# Arctos_65_V1.net
KiCad netlist of a schematic drawn in EAGLE
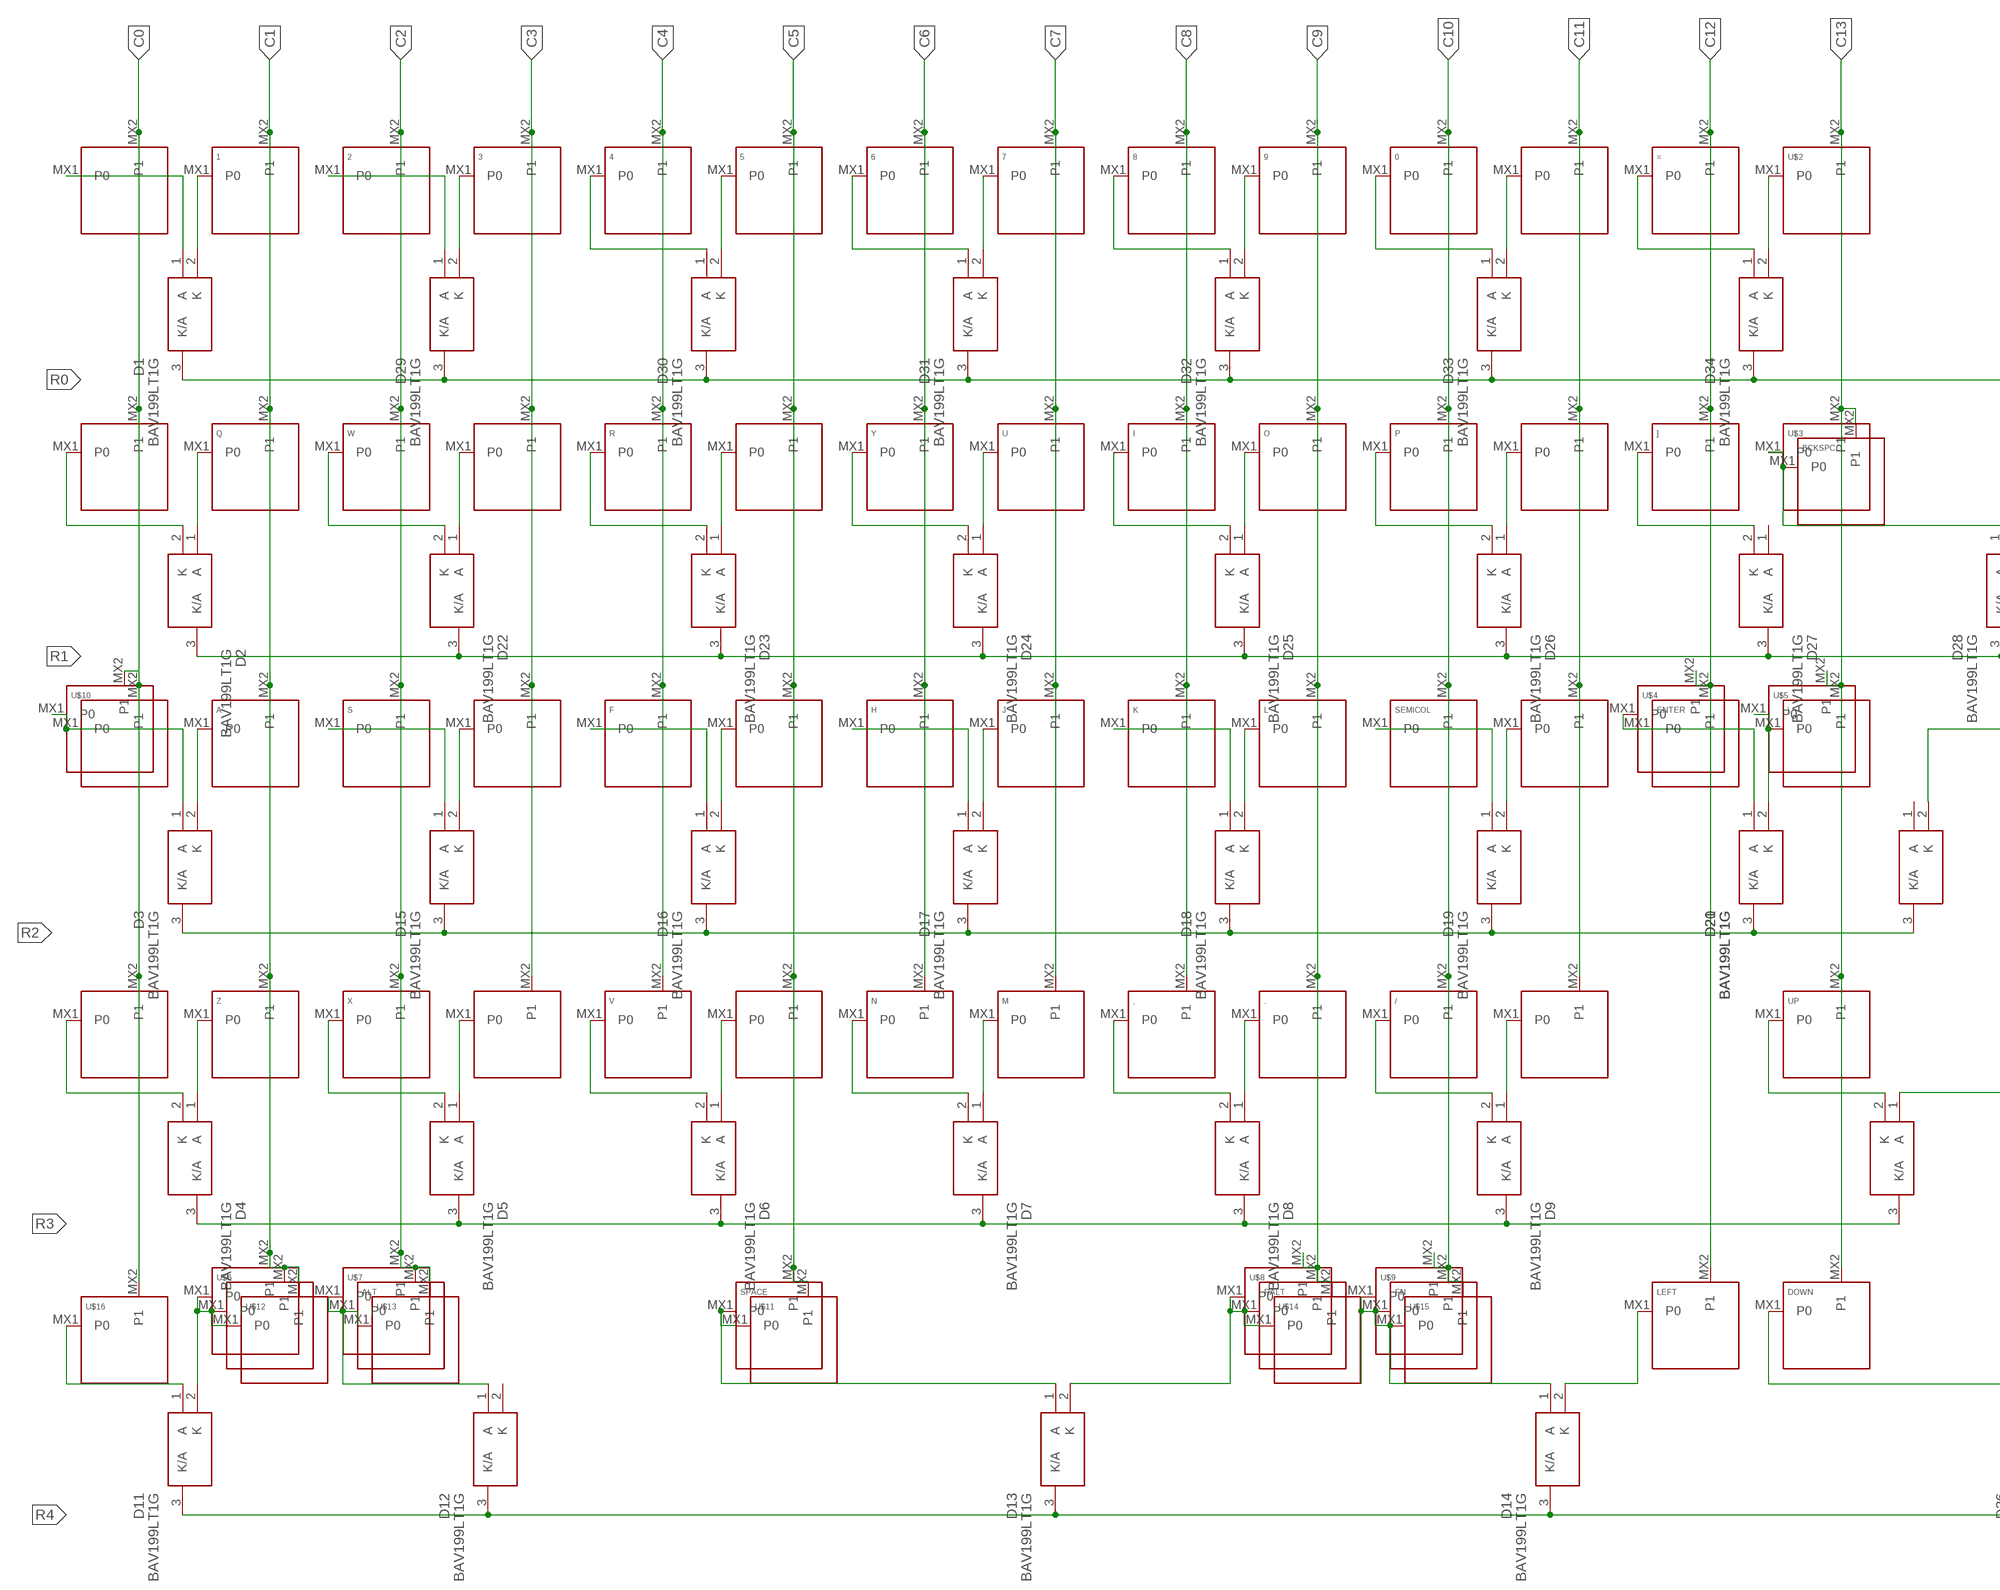
[diagram p0: schematic, sheet 1, part 1 of 2]
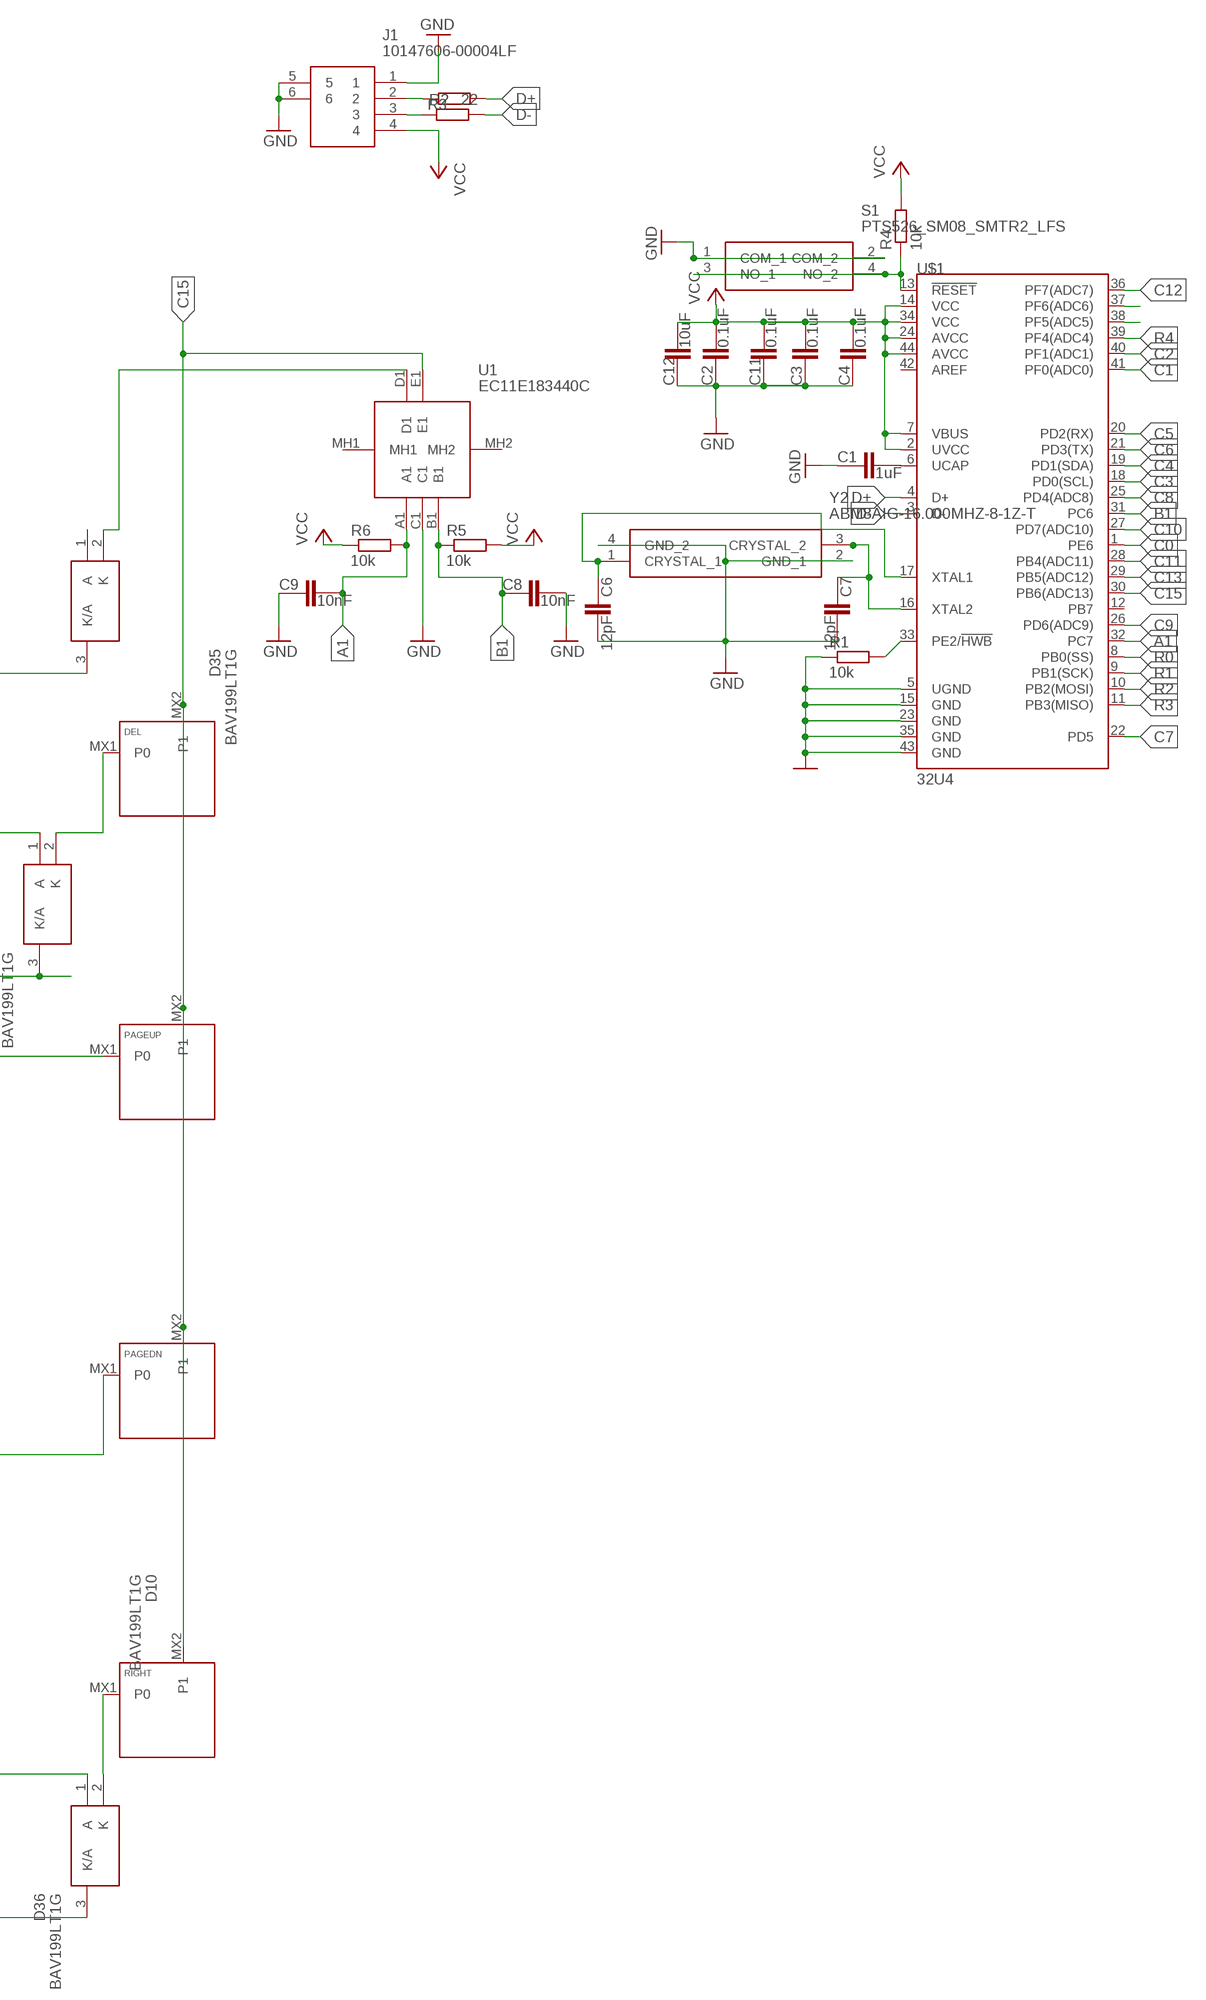
[diagram p1: schematic, sheet 1, part 2 of 2]

(export (version "E")
  (design (tool "Eeschema 10.0.6"))
  (components
    (comp (ref "'")
      (value "KEYSWITCH-PLAIN-MX-1U")
      (footprint "eagle-import:MX-1U")
      (libsource (lib "eagle-import") (part "KEYSWITCH-PLAIN-MX-1U"))
    )
    (comp (ref ",")
      (value "KEYSWITCH-PLAIN-MX-1U")
      (footprint "eagle-import:MX-1U")
      (libsource (lib "eagle-import") (part "KEYSWITCH-PLAIN-MX-1U"))
    )
    (comp (ref "-")
      (value "KEYSWITCH-PLAIN-MX-1U")
      (footprint "eagle-import:MX-1U")
      (libsource (lib "eagle-import") (part "KEYSWITCH-PLAIN-MX-1U"))
    )
    (comp (ref ".")
      (value "KEYSWITCH-PLAIN-MX-1U")
      (footprint "eagle-import:MX-1U")
      (libsource (lib "eagle-import") (part "KEYSWITCH-PLAIN-MX-1U"))
    )
    (comp (ref "/")
      (value "KEYSWITCH-PLAIN-MX-1U")
      (footprint "eagle-import:MX-1U")
      (libsource (lib "eagle-import") (part "KEYSWITCH-PLAIN-MX-1U"))
    )
    (comp (ref "0")
      (value "KEYSWITCH-PLAIN-MX-1U")
      (footprint "eagle-import:MX-1U")
      (libsource (lib "eagle-import") (part "KEYSWITCH-PLAIN-MX-1U"))
    )
    (comp (ref "1")
      (value "KEYSWITCH-PLAIN-MX-1U")
      (footprint "eagle-import:MX-1U")
      (libsource (lib "eagle-import") (part "KEYSWITCH-PLAIN-MX-1U"))
    )
    (comp (ref "2")
      (value "KEYSWITCH-PLAIN-MX-1U")
      (footprint "eagle-import:MX-1U")
      (libsource (lib "eagle-import") (part "KEYSWITCH-PLAIN-MX-1U"))
    )
    (comp (ref "3")
      (value "KEYSWITCH-PLAIN-MX-1U")
      (footprint "eagle-import:MX-1U")
      (libsource (lib "eagle-import") (part "KEYSWITCH-PLAIN-MX-1U"))
    )
    (comp (ref "4")
      (value "KEYSWITCH-PLAIN-MX-1U")
      (footprint "eagle-import:MX-1U")
      (libsource (lib "eagle-import") (part "KEYSWITCH-PLAIN-MX-1U"))
    )
    (comp (ref "5")
      (value "KEYSWITCH-PLAIN-MX-1U")
      (footprint "eagle-import:MX-1U")
      (libsource (lib "eagle-import") (part "KEYSWITCH-PLAIN-MX-1U"))
    )
    (comp (ref "6")
      (value "KEYSWITCH-PLAIN-MX-1U")
      (footprint "eagle-import:MX-1U")
      (libsource (lib "eagle-import") (part "KEYSWITCH-PLAIN-MX-1U"))
    )
    (comp (ref "7")
      (value "KEYSWITCH-PLAIN-MX-1U")
      (footprint "eagle-import:MX-1U")
      (libsource (lib "eagle-import") (part "KEYSWITCH-PLAIN-MX-1U"))
    )
    (comp (ref "8")
      (value "KEYSWITCH-PLAIN-MX-1U")
      (footprint "eagle-import:MX-1U")
      (libsource (lib "eagle-import") (part "KEYSWITCH-PLAIN-MX-1U"))
    )
    (comp (ref "9")
      (value "KEYSWITCH-PLAIN-MX-1U")
      (footprint "eagle-import:MX-1U")
      (libsource (lib "eagle-import") (part "KEYSWITCH-PLAIN-MX-1U"))
    )
    (comp (ref "=")
      (value "KEYSWITCH-PLAIN-MX-1U")
      (footprint "eagle-import:MX-1U")
      (libsource (lib "eagle-import") (part "KEYSWITCH-PLAIN-MX-1U"))
    )
    (comp (ref "A")
      (value "KEYSWITCH-PLAIN-MX-1U")
      (footprint "eagle-import:MX-1U")
      (libsource (lib "eagle-import") (part "KEYSWITCH-PLAIN-MX-1U"))
    )
    (comp (ref "ALT")
      (value "KEYSWITCH-PLAIN-MX-1U")
      (footprint "eagle-import:MX-1U")
      (libsource (lib "eagle-import") (part "KEYSWITCH-PLAIN-MX-1U"))
    )
    (comp (ref "B")
      (value "KEYSWITCH-PLAIN-MX-1U")
      (footprint "eagle-import:MX-1U")
      (libsource (lib "eagle-import") (part "KEYSWITCH-PLAIN-MX-1U"))
    )
    (comp (ref "BCKSPC")
      (value "KEYSWITCH-PLAIN-MX-2U")
      (footprint "eagle-import:MX-2U")
      (libsource (lib "eagle-import") (part "KEYSWITCH-PLAIN-MX-2U"))
    )
    (comp (ref "C")
      (value "KEYSWITCH-PLAIN-MX-1U")
      (footprint "eagle-import:MX-1U")
      (libsource (lib "eagle-import") (part "KEYSWITCH-PLAIN-MX-1U"))
    )
    (comp (ref "C1")
      (value "1uF")
      (footprint "eagle-import:C0603")
      (libsource (lib "eagle-import") (part "CAPACITOR-0603"))
    )
    (comp (ref "C2")
      (value "0.1uF")
      (footprint "eagle-import:C0603")
      (libsource (lib "eagle-import") (part "CAPACITOR-0603"))
    )
    (comp (ref "C3")
      (value "0.1uF")
      (footprint "eagle-import:C0603")
      (libsource (lib "eagle-import") (part "CAPACITOR-0603"))
    )
    (comp (ref "C4")
      (value "0.1uF")
      (footprint "eagle-import:C0603")
      (libsource (lib "eagle-import") (part "CAPACITOR-0603"))
    )
    (comp (ref "C6")
      (value "12pF")
      (footprint "eagle-import:C0603")
      (libsource (lib "eagle-import") (part "CAPACITOR-0603"))
    )
    (comp (ref "C7")
      (value "12pF")
      (footprint "eagle-import:C0603")
      (libsource (lib "eagle-import") (part "CAPACITOR-0603"))
    )
    (comp (ref "C8")
      (value "10nF")
      (footprint "eagle-import:C0603")
      (libsource (lib "eagle-import") (part "CAPACITOR-0603"))
    )
    (comp (ref "C9")
      (value "10nF")
      (footprint "eagle-import:C0603")
      (libsource (lib "eagle-import") (part "CAPACITOR-0603"))
    )
    (comp (ref "C11")
      (value "0.1uF")
      (footprint "eagle-import:C0603")
      (libsource (lib "eagle-import") (part "CAPACITOR-0603"))
    )
    (comp (ref "C12")
      (value "10uF")
      (footprint "eagle-import:C0603")
      (libsource (lib "eagle-import") (part "CAPACITOR-0603"))
    )
    (comp (ref "CAPS")
      (value "KEYSWITCH-PLAIN-MX-1U")
      (footprint "eagle-import:MX-1U")
      (libsource (lib "eagle-import") (part "KEYSWITCH-PLAIN-MX-1U"))
    )
    (comp (ref "D")
      (value "KEYSWITCH-PLAIN-MX-1U")
      (footprint "eagle-import:MX-1U")
      (libsource (lib "eagle-import") (part "KEYSWITCH-PLAIN-MX-1U"))
    )
    (comp (ref "D1")
      (value "BAV199LT1G")
      (footprint "eagle-import:SOT96P237X111-3N")
      (fields (field (name "MOUSER_PART_NUMBER") "863-BAV199LT1G"))
      (libsource (lib "eagle-import") (part "BAV199LT1G"))
    )
    (comp (ref "D2")
      (value "BAV199LT1G")
      (footprint "eagle-import:SOT96P237X111-3N")
      (fields (field (name "MOUSER_PART_NUMBER") "863-BAV199LT1G"))
      (libsource (lib "eagle-import") (part "BAV199LT1G"))
    )
    (comp (ref "D3")
      (value "BAV199LT1G")
      (footprint "eagle-import:SOT96P237X111-3N")
      (fields (field (name "MOUSER_PART_NUMBER") "863-BAV199LT1G"))
      (libsource (lib "eagle-import") (part "BAV199LT1G"))
    )
    (comp (ref "D4")
      (value "BAV199LT1G")
      (footprint "eagle-import:SOT96P237X111-3N")
      (fields (field (name "MOUSER_PART_NUMBER") "863-BAV199LT1G"))
      (libsource (lib "eagle-import") (part "BAV199LT1G"))
    )
    (comp (ref "D5")
      (value "BAV199LT1G")
      (footprint "eagle-import:SOT96P237X111-3N")
      (fields (field (name "MOUSER_PART_NUMBER") "863-BAV199LT1G"))
      (libsource (lib "eagle-import") (part "BAV199LT1G"))
    )
    (comp (ref "D6")
      (value "BAV199LT1G")
      (footprint "eagle-import:SOT96P237X111-3N")
      (fields (field (name "MOUSER_PART_NUMBER") "863-BAV199LT1G"))
      (libsource (lib "eagle-import") (part "BAV199LT1G"))
    )
    (comp (ref "D7")
      (value "BAV199LT1G")
      (footprint "eagle-import:SOT96P237X111-3N")
      (fields (field (name "MOUSER_PART_NUMBER") "863-BAV199LT1G"))
      (libsource (lib "eagle-import") (part "BAV199LT1G"))
    )
    (comp (ref "D8")
      (value "BAV199LT1G")
      (footprint "eagle-import:SOT96P237X111-3N")
      (fields (field (name "MOUSER_PART_NUMBER") "863-BAV199LT1G"))
      (libsource (lib "eagle-import") (part "BAV199LT1G"))
    )
    (comp (ref "D9")
      (value "BAV199LT1G")
      (footprint "eagle-import:SOT96P237X111-3N")
      (fields (field (name "MOUSER_PART_NUMBER") "863-BAV199LT1G"))
      (libsource (lib "eagle-import") (part "BAV199LT1G"))
    )
    (comp (ref "D10")
      (value "BAV199LT1G")
      (footprint "eagle-import:SOT96P237X111-3N")
      (fields (field (name "MOUSER_PART_NUMBER") "863-BAV199LT1G"))
      (libsource (lib "eagle-import") (part "BAV199LT1G"))
    )
    (comp (ref "D11")
      (value "BAV199LT1G")
      (footprint "eagle-import:SOT96P237X111-3N")
      (fields (field (name "MOUSER_PART_NUMBER") "863-BAV199LT1G"))
      (libsource (lib "eagle-import") (part "BAV199LT1G"))
    )
    (comp (ref "D12")
      (value "BAV199LT1G")
      (footprint "eagle-import:SOT96P237X111-3N")
      (fields (field (name "MOUSER_PART_NUMBER") "863-BAV199LT1G"))
      (libsource (lib "eagle-import") (part "BAV199LT1G"))
    )
    (comp (ref "D13")
      (value "BAV199LT1G")
      (footprint "eagle-import:SOT96P237X111-3N")
      (fields (field (name "MOUSER_PART_NUMBER") "863-BAV199LT1G"))
      (libsource (lib "eagle-import") (part "BAV199LT1G"))
    )
    (comp (ref "D14")
      (value "BAV199LT1G")
      (footprint "eagle-import:SOT96P237X111-3N")
      (fields (field (name "MOUSER_PART_NUMBER") "863-BAV199LT1G"))
      (libsource (lib "eagle-import") (part "BAV199LT1G"))
    )
    (comp (ref "D15")
      (value "BAV199LT1G")
      (footprint "eagle-import:SOT96P237X111-3N")
      (fields (field (name "MOUSER_PART_NUMBER") "863-BAV199LT1G"))
      (libsource (lib "eagle-import") (part "BAV199LT1G"))
    )
    (comp (ref "D16")
      (value "BAV199LT1G")
      (footprint "eagle-import:SOT96P237X111-3N")
      (fields (field (name "MOUSER_PART_NUMBER") "863-BAV199LT1G"))
      (libsource (lib "eagle-import") (part "BAV199LT1G"))
    )
    (comp (ref "D17")
      (value "BAV199LT1G")
      (footprint "eagle-import:SOT96P237X111-3N")
      (fields (field (name "MOUSER_PART_NUMBER") "863-BAV199LT1G"))
      (libsource (lib "eagle-import") (part "BAV199LT1G"))
    )
    (comp (ref "D18")
      (value "BAV199LT1G")
      (footprint "eagle-import:SOT96P237X111-3N")
      (fields (field (name "MOUSER_PART_NUMBER") "863-BAV199LT1G"))
      (libsource (lib "eagle-import") (part "BAV199LT1G"))
    )
    (comp (ref "D19")
      (value "BAV199LT1G")
      (footprint "eagle-import:SOT96P237X111-3N")
      (fields (field (name "MOUSER_PART_NUMBER") "863-BAV199LT1G"))
      (libsource (lib "eagle-import") (part "BAV199LT1G"))
    )
    (comp (ref "D20")
      (value "BAV199LT1G")
      (footprint "eagle-import:SOT96P237X111-3N")
      (fields (field (name "MOUSER_PART_NUMBER") "863-BAV199LT1G"))
      (libsource (lib "eagle-import") (part "BAV199LT1G"))
    )
    (comp (ref "D21")
      (value "BAV199LT1G")
      (footprint "eagle-import:SOT96P237X111-3N")
      (fields (field (name "MOUSER_PART_NUMBER") "863-BAV199LT1G"))
      (libsource (lib "eagle-import") (part "BAV199LT1G"))
    )
    (comp (ref "D22")
      (value "BAV199LT1G")
      (footprint "eagle-import:SOT96P237X111-3N")
      (fields (field (name "MOUSER_PART_NUMBER") "863-BAV199LT1G"))
      (libsource (lib "eagle-import") (part "BAV199LT1G"))
    )
    (comp (ref "D23")
      (value "BAV199LT1G")
      (footprint "eagle-import:SOT96P237X111-3N")
      (fields (field (name "MOUSER_PART_NUMBER") "863-BAV199LT1G"))
      (libsource (lib "eagle-import") (part "BAV199LT1G"))
    )
    (comp (ref "D24")
      (value "BAV199LT1G")
      (footprint "eagle-import:SOT96P237X111-3N")
      (fields (field (name "MOUSER_PART_NUMBER") "863-BAV199LT1G"))
      (libsource (lib "eagle-import") (part "BAV199LT1G"))
    )
    (comp (ref "D25")
      (value "BAV199LT1G")
      (footprint "eagle-import:SOT96P237X111-3N")
      (fields (field (name "MOUSER_PART_NUMBER") "863-BAV199LT1G"))
      (libsource (lib "eagle-import") (part "BAV199LT1G"))
    )
    (comp (ref "D26")
      (value "BAV199LT1G")
      (footprint "eagle-import:SOT96P237X111-3N")
      (fields (field (name "MOUSER_PART_NUMBER") "863-BAV199LT1G"))
      (libsource (lib "eagle-import") (part "BAV199LT1G"))
    )
    (comp (ref "D27")
      (value "BAV199LT1G")
      (footprint "eagle-import:SOT96P237X111-3N")
      (fields (field (name "MOUSER_PART_NUMBER") "863-BAV199LT1G"))
      (libsource (lib "eagle-import") (part "BAV199LT1G"))
    )
    (comp (ref "D28")
      (value "BAV199LT1G")
      (footprint "eagle-import:SOT96P237X111-3N")
      (fields (field (name "MOUSER_PART_NUMBER") "863-BAV199LT1G"))
      (libsource (lib "eagle-import") (part "BAV199LT1G"))
    )
    (comp (ref "D29")
      (value "BAV199LT1G")
      (footprint "eagle-import:SOT96P237X111-3N")
      (fields (field (name "MOUSER_PART_NUMBER") "863-BAV199LT1G"))
      (libsource (lib "eagle-import") (part "BAV199LT1G"))
    )
    (comp (ref "D30")
      (value "BAV199LT1G")
      (footprint "eagle-import:SOT96P237X111-3N")
      (fields (field (name "MOUSER_PART_NUMBER") "863-BAV199LT1G"))
      (libsource (lib "eagle-import") (part "BAV199LT1G"))
    )
    (comp (ref "D31")
      (value "BAV199LT1G")
      (footprint "eagle-import:SOT96P237X111-3N")
      (fields (field (name "MOUSER_PART_NUMBER") "863-BAV199LT1G"))
      (libsource (lib "eagle-import") (part "BAV199LT1G"))
    )
    (comp (ref "D32")
      (value "BAV199LT1G")
      (footprint "eagle-import:SOT96P237X111-3N")
      (fields (field (name "MOUSER_PART_NUMBER") "863-BAV199LT1G"))
      (libsource (lib "eagle-import") (part "BAV199LT1G"))
    )
    (comp (ref "D33")
      (value "BAV199LT1G")
      (footprint "eagle-import:SOT96P237X111-3N")
      (fields (field (name "MOUSER_PART_NUMBER") "863-BAV199LT1G"))
      (libsource (lib "eagle-import") (part "BAV199LT1G"))
    )
    (comp (ref "D34")
      (value "BAV199LT1G")
      (footprint "eagle-import:SOT96P237X111-3N")
      (fields (field (name "MOUSER_PART_NUMBER") "863-BAV199LT1G"))
      (libsource (lib "eagle-import") (part "BAV199LT1G"))
    )
    (comp (ref "D35")
      (value "BAV199LT1G")
      (footprint "eagle-import:SOT96P237X111-3N")
      (fields (field (name "MOUSER_PART_NUMBER") "863-BAV199LT1G"))
      (libsource (lib "eagle-import") (part "BAV199LT1G"))
    )
    (comp (ref "D36")
      (value "BAV199LT1G")
      (footprint "eagle-import:SOT96P237X111-3N")
      (fields (field (name "MOUSER_PART_NUMBER") "863-BAV199LT1G"))
      (libsource (lib "eagle-import") (part "BAV199LT1G"))
    )
    (comp (ref "DEL")
      (value "KEYSWITCH-PLAIN-MX-1U")
      (footprint "eagle-import:MX-1U")
      (libsource (lib "eagle-import") (part "KEYSWITCH-PLAIN-MX-1U"))
    )
    (comp (ref "DOWN")
      (value "KEYSWITCH-PLAIN-MX-1U")
      (footprint "eagle-import:MX-1U")
      (libsource (lib "eagle-import") (part "KEYSWITCH-PLAIN-MX-1U"))
    )
    (comp (ref "E")
      (value "KEYSWITCH-PLAIN-MX-1U")
      (footprint "eagle-import:MX-1U")
      (libsource (lib "eagle-import") (part "KEYSWITCH-PLAIN-MX-1U"))
    )
    (comp (ref "ENTER")
      (value "KEYSWITCH-PLAIN-MX-2U")
      (footprint "eagle-import:MX-2U")
      (libsource (lib "eagle-import") (part "KEYSWITCH-PLAIN-MX-2U"))
    )
    (comp (ref "ESC")
      (value "KEYSWITCH-PLAIN-MX-1U")
      (footprint "eagle-import:MX-1U")
      (libsource (lib "eagle-import") (part "KEYSWITCH-PLAIN-MX-1U"))
    )
    (comp (ref "F")
      (value "KEYSWITCH-PLAIN-MX-1U")
      (footprint "eagle-import:MX-1U")
      (libsource (lib "eagle-import") (part "KEYSWITCH-PLAIN-MX-1U"))
    )
    (comp (ref "FN")
      (value "KEYSWITCH-PLAIN-MX-1U")
      (footprint "eagle-import:MX-1U")
      (libsource (lib "eagle-import") (part "KEYSWITCH-PLAIN-MX-1U"))
    )
    (comp (ref "G")
      (value "KEYSWITCH-PLAIN-MX-1U")
      (footprint "eagle-import:MX-1U")
      (libsource (lib "eagle-import") (part "KEYSWITCH-PLAIN-MX-1U"))
    )
    (comp (ref "H")
      (value "KEYSWITCH-PLAIN-MX-1U")
      (footprint "eagle-import:MX-1U")
      (libsource (lib "eagle-import") (part "KEYSWITCH-PLAIN-MX-1U"))
    )
    (comp (ref "I")
      (value "KEYSWITCH-PLAIN-MX-1U")
      (footprint "eagle-import:MX-1U")
      (libsource (lib "eagle-import") (part "KEYSWITCH-PLAIN-MX-1U"))
    )
    (comp (ref "J")
      (value "KEYSWITCH-PLAIN-MX-1U")
      (footprint "eagle-import:MX-1U")
      (libsource (lib "eagle-import") (part "KEYSWITCH-PLAIN-MX-1U"))
    )
    (comp (ref "J1")
      (value "10147606-00004LF")
      (footprint "eagle-import:1014760600004LF")
      (fields (field (name "MOUSER_PART_NUMBER") "649-10147606-00004LF"))
      (libsource (lib "eagle-import") (part "10147606-00004LF"))
    )
    (comp (ref "K")
      (value "KEYSWITCH-PLAIN-MX-1U")
      (footprint "eagle-import:MX-1U")
      (libsource (lib "eagle-import") (part "KEYSWITCH-PLAIN-MX-1U"))
    )
    (comp (ref "L")
      (value "KEYSWITCH-PLAIN-MX-1U")
      (footprint "eagle-import:MX-1U")
      (libsource (lib "eagle-import") (part "KEYSWITCH-PLAIN-MX-1U"))
    )
    (comp (ref "LEFT")
      (value "KEYSWITCH-PLAIN-MX-1U")
      (footprint "eagle-import:MX-1U")
      (libsource (lib "eagle-import") (part "KEYSWITCH-PLAIN-MX-1U"))
    )
    (comp (ref "M")
      (value "KEYSWITCH-PLAIN-MX-1U")
      (footprint "eagle-import:MX-1U")
      (libsource (lib "eagle-import") (part "KEYSWITCH-PLAIN-MX-1U"))
    )
    (comp (ref "N")
      (value "KEYSWITCH-PLAIN-MX-1U")
      (footprint "eagle-import:MX-1U")
      (libsource (lib "eagle-import") (part "KEYSWITCH-PLAIN-MX-1U"))
    )
    (comp (ref "O")
      (value "KEYSWITCH-PLAIN-MX-1U")
      (footprint "eagle-import:MX-1U")
      (libsource (lib "eagle-import") (part "KEYSWITCH-PLAIN-MX-1U"))
    )
    (comp (ref "P")
      (value "KEYSWITCH-PLAIN-MX-1U")
      (footprint "eagle-import:MX-1U")
      (libsource (lib "eagle-import") (part "KEYSWITCH-PLAIN-MX-1U"))
    )
    (comp (ref "PAGEDN")
      (value "KEYSWITCH-PLAIN-MX-1U")
      (footprint "eagle-import:MX-1U")
      (libsource (lib "eagle-import") (part "KEYSWITCH-PLAIN-MX-1U"))
    )
    (comp (ref "PAGEUP")
      (value "KEYSWITCH-PLAIN-MX-1U")
      (footprint "eagle-import:MX-1U")
      (libsource (lib "eagle-import") (part "KEYSWITCH-PLAIN-MX-1U"))
    )
    (comp (ref "Q")
      (value "KEYSWITCH-PLAIN-MX-1U")
      (footprint "eagle-import:MX-1U")
      (libsource (lib "eagle-import") (part "KEYSWITCH-PLAIN-MX-1U"))
    )
    (comp (ref "R")
      (value "KEYSWITCH-PLAIN-MX-1U")
      (footprint "eagle-import:MX-1U")
      (libsource (lib "eagle-import") (part "KEYSWITCH-PLAIN-MX-1U"))
    )
    (comp (ref "R1")
      (value "10k")
      (footprint "eagle-import:R0603")
      (libsource (lib "eagle-import") (part "RESISTOR-0603"))
    )
    (comp (ref "R2")
      (value "22")
      (footprint "eagle-import:R0603")
      (libsource (lib "eagle-import") (part "RESISTOR-0603"))
    )
    (comp (ref "R3")
      (value "22")
      (footprint "eagle-import:R0603")
      (libsource (lib "eagle-import") (part "RESISTOR-0603"))
    )
    (comp (ref "R4")
      (value "10k")
      (footprint "eagle-import:R0603")
      (libsource (lib "eagle-import") (part "RESISTOR-0603"))
    )
    (comp (ref "R5")
      (value "10k")
      (footprint "eagle-import:R0603")
      (libsource (lib "eagle-import") (part "RESISTOR-0603"))
    )
    (comp (ref "R6")
      (value "10k")
      (footprint "eagle-import:R0603")
      (libsource (lib "eagle-import") (part "RESISTOR-0603"))
    )
    (comp (ref "RALT")
      (value "KEYSWITCH-PLAIN-MX-1U")
      (footprint "eagle-import:MX-1U")
      (libsource (lib "eagle-import") (part "KEYSWITCH-PLAIN-MX-1U"))
    )
    (comp (ref "RIGHT")
      (value "KEYSWITCH-PLAIN-MX-1U")
      (footprint "eagle-import:MX-1U")
      (libsource (lib "eagle-import") (part "KEYSWITCH-PLAIN-MX-1U"))
    )
    (comp (ref "RSHIFT")
      (value "KEYSWITCH-PLAIN-MX-1U")
      (footprint "eagle-import:MX-1U")
      (libsource (lib "eagle-import") (part "KEYSWITCH-PLAIN-MX-1U"))
    )
    (comp (ref "S")
      (value "KEYSWITCH-PLAIN-MX-1U")
      (footprint "eagle-import:MX-1U")
      (libsource (lib "eagle-import") (part "KEYSWITCH-PLAIN-MX-1U"))
    )
    (comp (ref "S1")
      (value "PTS526_SM08_SMTR2_LFS")
      (footprint "eagle-import:PTS526SM08SMTR2LFS")
      (fields
        (field (name "MANUFACTURER_PART_NUMBER") "PTS526 SM08 SMTR2 LFS")
        (field (name "MOUSER_PART_NUMBER") "611-PTS526SM08SMTR2L")
      )
      (libsource (lib "eagle-import") (part "PTS526_SM08_SMTR2_LFS"))
    )
    (comp (ref "SEMICOL")
      (value "KEYSWITCH-PLAIN-MX-1U")
      (footprint "eagle-import:MX-1U")
      (libsource (lib "eagle-import") (part "KEYSWITCH-PLAIN-MX-1U"))
    )
    (comp (ref "SHIFT")
      (value "KEYSWITCH-PLAIN-MX-2U")
      (footprint "eagle-import:MX-2U")
      (libsource (lib "eagle-import") (part "KEYSWITCH-PLAIN-MX-2U"))
    )
    (comp (ref "SPACE")
      (value "KEYSWITCH-PLAIN-MX-7U-FLIPPED")
      (footprint "eagle-import:MX-7U-FLIPPED")
      (libsource (lib "eagle-import") (part "KEYSWITCH-PLAIN-MX-7U-FLIPPED"))
    )
    (comp (ref "T")
      (value "KEYSWITCH-PLAIN-MX-1U")
      (footprint "eagle-import:MX-1U")
      (libsource (lib "eagle-import") (part "KEYSWITCH-PLAIN-MX-1U"))
    )
    (comp (ref "TAB")
      (value "KEYSWITCH-PLAIN-MX-1U")
      (footprint "eagle-import:MX-1U")
      (libsource (lib "eagle-import") (part "KEYSWITCH-PLAIN-MX-1U"))
    )
    (comp (ref "U")
      (value "KEYSWITCH-PLAIN-MX-1U")
      (footprint "eagle-import:MX-1U")
      (libsource (lib "eagle-import") (part "KEYSWITCH-PLAIN-MX-1U"))
    )
    (comp (ref "U$1")
      (value "32U4")
      (footprint "eagle-import:TQFP44")
      (libsource (lib "eagle-import") (part "ATMEGA32U4TQFP-44"))
    )
    (comp (ref "U$2")
      (value "KEYSWITCH-PLAIN-MX-1U")
      (footprint "eagle-import:MX-1U")
      (libsource (lib "eagle-import") (part "KEYSWITCH-PLAIN-MX-1U"))
    )
    (comp (ref "U$3")
      (value "KEYSWITCH-PLAIN-MX-1U")
      (footprint "eagle-import:MX-1U")
      (libsource (lib "eagle-import") (part "KEYSWITCH-PLAIN-MX-1U"))
    )
    (comp (ref "U$4")
      (value "KEYSWITCH-PLAIN-MX-1U")
      (footprint "eagle-import:MX-1U")
      (libsource (lib "eagle-import") (part "KEYSWITCH-PLAIN-MX-1U"))
    )
    (comp (ref "U$5")
      (value "KEYSWITCH-PLAIN-MX-2U-ROTATED")
      (footprint "eagle-import:MX-2U-ROTATED")
      (libsource (lib "eagle-import") (part "KEYSWITCH-PLAIN-MX-2U-ROTATED"))
    )
    (comp (ref "U$6")
      (value "KEYSWITCH-PLAIN-MX-1U")
      (footprint "eagle-import:MX-1U")
      (libsource (lib "eagle-import") (part "KEYSWITCH-PLAIN-MX-1U"))
    )
    (comp (ref "U$7")
      (value "KEYSWITCH-PLAIN-MX-1U")
      (footprint "eagle-import:MX-1U")
      (libsource (lib "eagle-import") (part "KEYSWITCH-PLAIN-MX-1U"))
    )
    (comp (ref "U$8")
      (value "KEYSWITCH-PLAIN-MX-1U")
      (footprint "eagle-import:MX-1U")
      (libsource (lib "eagle-import") (part "KEYSWITCH-PLAIN-MX-1U"))
    )
    (comp (ref "U$9")
      (value "KEYSWITCH-PLAIN-MX-1U")
      (footprint "eagle-import:MX-1U")
      (libsource (lib "eagle-import") (part "KEYSWITCH-PLAIN-MX-1U"))
    )
    (comp (ref "U$10")
      (value "KEYSWITCH-PLAIN-MX-1U")
      (footprint "eagle-import:MX-1U")
      (libsource (lib "eagle-import") (part "KEYSWITCH-PLAIN-MX-1U"))
    )
    (comp (ref "U$11")
      (value "KEYSWITCH-PLAIN-MX-6.25U-FLIPPED")
      (footprint "eagle-import:MX-6.25U-FLIPPED")
      (libsource (lib "eagle-import") (part "KEYSWITCH-PLAIN-MX-6.25U-FLIPPED"))
    )
    (comp (ref "U$12")
      (value "KEYSWITCH-PLAIN-MX-1U")
      (footprint "eagle-import:MX-1U")
      (libsource (lib "eagle-import") (part "KEYSWITCH-PLAIN-MX-1U"))
    )
    (comp (ref "U$13")
      (value "KEYSWITCH-PLAIN-MX-1U")
      (footprint "eagle-import:MX-1U")
      (libsource (lib "eagle-import") (part "KEYSWITCH-PLAIN-MX-1U"))
    )
    (comp (ref "U$14")
      (value "KEYSWITCH-PLAIN-MX-1U")
      (footprint "eagle-import:MX-1U")
      (libsource (lib "eagle-import") (part "KEYSWITCH-PLAIN-MX-1U"))
    )
    (comp (ref "U$15")
      (value "KEYSWITCH-PLAIN-MX-1U")
      (footprint "eagle-import:MX-1U")
      (libsource (lib "eagle-import") (part "KEYSWITCH-PLAIN-MX-1U"))
    )
    (comp (ref "U$16")
      (value "KEYSWITCH-PLAIN-MX-1U")
      (footprint "eagle-import:MX-1U")
      (libsource (lib "eagle-import") (part "KEYSWITCH-PLAIN-MX-1U"))
    )
    (comp (ref "U1")
      (value "EC11E183440C")
      (footprint "eagle-import:EC11E183440C")
      (fields (field (name "MOUSER_PART_NUMBER") "688-EC11E183440C"))
      (libsource (lib "eagle-import") (part "EC11E183440C"))
    )
    (comp (ref "UP")
      (value "KEYSWITCH-PLAIN-MX-1U")
      (footprint "eagle-import:MX-1U")
      (libsource (lib "eagle-import") (part "KEYSWITCH-PLAIN-MX-1U"))
    )
    (comp (ref "V")
      (value "KEYSWITCH-PLAIN-MX-1U")
      (footprint "eagle-import:MX-1U")
      (libsource (lib "eagle-import") (part "KEYSWITCH-PLAIN-MX-1U"))
    )
    (comp (ref "W")
      (value "KEYSWITCH-PLAIN-MX-1U")
      (footprint "eagle-import:MX-1U")
      (libsource (lib "eagle-import") (part "KEYSWITCH-PLAIN-MX-1U"))
    )
    (comp (ref "WIN")
      (value "KEYSWITCH-PLAIN-MX-1U")
      (footprint "eagle-import:MX-1U")
      (libsource (lib "eagle-import") (part "KEYSWITCH-PLAIN-MX-1U"))
    )
    (comp (ref "X")
      (value "KEYSWITCH-PLAIN-MX-1U")
      (footprint "eagle-import:MX-1U")
      (libsource (lib "eagle-import") (part "KEYSWITCH-PLAIN-MX-1U"))
    )
    (comp (ref "Y")
      (value "KEYSWITCH-PLAIN-MX-1U")
      (footprint "eagle-import:MX-1U")
      (libsource (lib "eagle-import") (part "KEYSWITCH-PLAIN-MX-1U"))
    )
    (comp (ref "Y2")
      (value "ABM8AIG-16.000MHZ-8-1Z-T")
      (footprint "eagle-import:ABM8AIG16000MHZ81ZT")
      (fields (field (name "MOUSER_PART_NUMBER") "815-M8AIG-16-8-1ZT"))
      (libsource (lib "eagle-import") (part "ABM8AIG-16.000MHZ-8-1Z-T"))
    )
    (comp (ref "Z")
      (value "KEYSWITCH-PLAIN-MX-1U")
      (footprint "eagle-import:MX-1U")
      (libsource (lib "eagle-import") (part "KEYSWITCH-PLAIN-MX-1U"))
    )
    (comp (ref "[")
      (value "KEYSWITCH-PLAIN-MX-1U")
      (footprint "eagle-import:MX-1U")
      (libsource (lib "eagle-import") (part "KEYSWITCH-PLAIN-MX-1U"))
    )
    (comp (ref "\\")
      (value "KEYSWITCH-PLAIN-MX-1U")
      (footprint "eagle-import:MX-1U")
      (libsource (lib "eagle-import") (part "KEYSWITCH-PLAIN-MX-1U"))
    )
    (comp (ref "]")
      (value "KEYSWITCH-PLAIN-MX-1U")
      (footprint "eagle-import:MX-1U")
      (libsource (lib "eagle-import") (part "KEYSWITCH-PLAIN-MX-1U"))
    )
  )
  (nets
    (net (code "1") (name "A1") (class "Default")
      (node (ref "C9") (pin "2") (pinfunction "2_2") (pintype "passive"))
      (node (ref "R6") (pin "2") (pinfunction "2_2") (pintype "passive"))
      (node (ref "U$1") (pin "32") (pinfunction "PC7_32") (pintype "bidirectional"))
      (node (ref "U1") (pin "A1") (pinfunction "A1_A1") (pintype "bidirectional"))
    )
    (net (code "2") (name "B1") (class "Default")
      (node (ref "C8") (pin "1") (pinfunction "1_1") (pintype "passive"))
      (node (ref "R5") (pin "1") (pinfunction "1_1") (pintype "passive"))
      (node (ref "U$1") (pin "31") (pinfunction "PC6_31") (pintype "bidirectional"))
      (node (ref "U1") (pin "B1") (pinfunction "B1_B1") (pintype "bidirectional"))
    )
    (net (code "3") (name "C0") (class "Default")
      (node (ref "CAPS") (pin "MX2") (pinfunction "P1_MX2") (pintype "bidirectional"))
      (node (ref "ESC") (pin "MX2") (pinfunction "P1_MX2") (pintype "bidirectional"))
      (node (ref "SHIFT") (pin "MX2") (pinfunction "P1_MX2") (pintype "bidirectional"))
      (node (ref "TAB") (pin "MX2") (pinfunction "P1_MX2") (pintype "bidirectional"))
      (node (ref "U$1") (pin "1") (pinfunction "PE6_1") (pintype "bidirectional"))
      (node (ref "U$10") (pin "MX2") (pinfunction "P1_MX2") (pintype "bidirectional"))
      (node (ref "U$16") (pin "MX2") (pinfunction "P1_MX2") (pintype "bidirectional"))
    )
    (net (code "4") (name "C1") (class "Default")
      (node (ref "1") (pin "MX2") (pinfunction "P1_MX2") (pintype "bidirectional"))
      (node (ref "A") (pin "MX2") (pinfunction "P1_MX2") (pintype "bidirectional"))
      (node (ref "Q") (pin "MX2") (pinfunction "P1_MX2") (pintype "bidirectional"))
      (node (ref "U$1") (pin "41") (pinfunction "PF0(ADC0)_41") (pintype "bidirectional"))
      (node (ref "U$12") (pin "MX2") (pinfunction "P1_MX2") (pintype "bidirectional"))
      (node (ref "U$6") (pin "MX2") (pinfunction "P1_MX2") (pintype "bidirectional"))
      (node (ref "WIN") (pin "MX2") (pinfunction "P1_MX2") (pintype "bidirectional"))
      (node (ref "Z") (pin "MX2") (pinfunction "P1_MX2") (pintype "bidirectional"))
    )
    (net (code "5") (name "C2") (class "Default")
      (node (ref "2") (pin "MX2") (pinfunction "P1_MX2") (pintype "bidirectional"))
      (node (ref "ALT") (pin "MX2") (pinfunction "P1_MX2") (pintype "bidirectional"))
      (node (ref "S") (pin "MX2") (pinfunction "P1_MX2") (pintype "bidirectional"))
      (node (ref "U$1") (pin "40") (pinfunction "PF1(ADC1)_40") (pintype "bidirectional"))
      (node (ref "U$13") (pin "MX2") (pinfunction "P1_MX2") (pintype "bidirectional"))
      (node (ref "U$7") (pin "MX2") (pinfunction "P1_MX2") (pintype "bidirectional"))
      (node (ref "W") (pin "MX2") (pinfunction "P1_MX2") (pintype "bidirectional"))
      (node (ref "X") (pin "MX2") (pinfunction "P1_MX2") (pintype "bidirectional"))
    )
    (net (code "6") (name "C3") (class "Default")
      (node (ref "3") (pin "MX2") (pinfunction "P1_MX2") (pintype "bidirectional"))
      (node (ref "C") (pin "MX2") (pinfunction "P1_MX2") (pintype "bidirectional"))
      (node (ref "D") (pin "MX2") (pinfunction "P1_MX2") (pintype "bidirectional"))
      (node (ref "E") (pin "MX2") (pinfunction "P1_MX2") (pintype "bidirectional"))
      (node (ref "U$1") (pin "18") (pinfunction "PD0(SCL)_18") (pintype "bidirectional"))
    )
    (net (code "7") (name "C4") (class "Default")
      (node (ref "4") (pin "MX2") (pinfunction "P1_MX2") (pintype "bidirectional"))
      (node (ref "F") (pin "MX2") (pinfunction "P1_MX2") (pintype "bidirectional"))
      (node (ref "R") (pin "MX2") (pinfunction "P1_MX2") (pintype "bidirectional"))
      (node (ref "U$1") (pin "19") (pinfunction "PD1(SDA)_19") (pintype "bidirectional"))
      (node (ref "V") (pin "MX2") (pinfunction "P1_MX2") (pintype "bidirectional"))
    )
    (net (code "8") (name "C5") (class "Default")
      (node (ref "5") (pin "MX2") (pinfunction "P1_MX2") (pintype "bidirectional"))
      (node (ref "B") (pin "MX2") (pinfunction "P1_MX2") (pintype "bidirectional"))
      (node (ref "G") (pin "MX2") (pinfunction "P1_MX2") (pintype "bidirectional"))
      (node (ref "SPACE") (pin "MX2") (pinfunction "P1_MX2") (pintype "bidirectional"))
      (node (ref "T") (pin "MX2") (pinfunction "P1_MX2") (pintype "bidirectional"))
      (node (ref "U$1") (pin "20") (pinfunction "PD2(RX)_20") (pintype "bidirectional"))
      (node (ref "U$11") (pin "MX2") (pinfunction "P1_MX2") (pintype "bidirectional"))
    )
    (net (code "9") (name "C6") (class "Default")
      (node (ref "6") (pin "MX2") (pinfunction "P1_MX2") (pintype "bidirectional"))
      (node (ref "H") (pin "MX2") (pinfunction "P1_MX2") (pintype "bidirectional"))
      (node (ref "N") (pin "MX2") (pinfunction "P1_MX2") (pintype "bidirectional"))
      (node (ref "U$1") (pin "21") (pinfunction "PD3(TX)_21") (pintype "bidirectional"))
      (node (ref "Y") (pin "MX2") (pinfunction "P1_MX2") (pintype "bidirectional"))
    )
    (net (code "10") (name "C7") (class "Default")
      (node (ref "7") (pin "MX2") (pinfunction "P1_MX2") (pintype "bidirectional"))
      (node (ref "J") (pin "MX2") (pinfunction "P1_MX2") (pintype "bidirectional"))
      (node (ref "M") (pin "MX2") (pinfunction "P1_MX2") (pintype "bidirectional"))
      (node (ref "U") (pin "MX2") (pinfunction "P1_MX2") (pintype "bidirectional"))
      (node (ref "U$1") (pin "22") (pinfunction "PD5_22") (pintype "bidirectional"))
    )
    (net (code "11") (name "C8") (class "Default")
      (node (ref ",") (pin "MX2") (pinfunction "P1_MX2") (pintype "bidirectional"))
      (node (ref "8") (pin "MX2") (pinfunction "P1_MX2") (pintype "bidirectional"))
      (node (ref "I") (pin "MX2") (pinfunction "P1_MX2") (pintype "bidirectional"))
      (node (ref "K") (pin "MX2") (pinfunction "P1_MX2") (pintype "bidirectional"))
      (node (ref "U$1") (pin "25") (pinfunction "PD4(ADC8)_25") (pintype "bidirectional"))
    )
    (net (code "12") (name "C9") (class "Default")
      (node (ref ".") (pin "MX2") (pinfunction "P1_MX2") (pintype "bidirectional"))
      (node (ref "9") (pin "MX2") (pinfunction "P1_MX2") (pintype "bidirectional"))
      (node (ref "L") (pin "MX2") (pinfunction "P1_MX2") (pintype "bidirectional"))
      (node (ref "O") (pin "MX2") (pinfunction "P1_MX2") (pintype "bidirectional"))
      (node (ref "RALT") (pin "MX2") (pinfunction "P1_MX2") (pintype "bidirectional"))
      (node (ref "U$1") (pin "26") (pinfunction "PD6(ADC9)_26") (pintype "bidirectional"))
      (node (ref "U$14") (pin "MX2") (pinfunction "P1_MX2") (pintype "bidirectional"))
      (node (ref "U$8") (pin "MX2") (pinfunction "P1_MX2") (pintype "bidirectional"))
    )
    (net (code "13") (name "C10") (class "Default")
      (node (ref "/") (pin "MX2") (pinfunction "P1_MX2") (pintype "bidirectional"))
      (node (ref "0") (pin "MX2") (pinfunction "P1_MX2") (pintype "bidirectional"))
      (node (ref "FN") (pin "MX2") (pinfunction "P1_MX2") (pintype "bidirectional"))
      (node (ref "P") (pin "MX2") (pinfunction "P1_MX2") (pintype "bidirectional"))
      (node (ref "SEMICOL") (pin "MX2") (pinfunction "P1_MX2") (pintype "bidirectional"))
      (node (ref "U$1") (pin "27") (pinfunction "PD7(ADC10)_27") (pintype "bidirectional"))
      (node (ref "U$15") (pin "MX2") (pinfunction "P1_MX2") (pintype "bidirectional"))
      (node (ref "U$9") (pin "MX2") (pinfunction "P1_MX2") (pintype "bidirectional"))
    )
    (net (code "14") (name "C11") (class "Default")
      (node (ref "'") (pin "MX2") (pinfunction "P1_MX2") (pintype "bidirectional"))
      (node (ref "-") (pin "MX2") (pinfunction "P1_MX2") (pintype "bidirectional"))
      (node (ref "RSHIFT") (pin "MX2") (pinfunction "P1_MX2") (pintype "bidirectional"))
      (node (ref "U$1") (pin "28") (pinfunction "PB4(ADC11)_28") (pintype "bidirectional"))
      (node (ref "[") (pin "MX2") (pinfunction "P1_MX2") (pintype "bidirectional"))
    )
    (net (code "15") (name "C12") (class "Default")
      (node (ref "=") (pin "MX2") (pinfunction "P1_MX2") (pintype "bidirectional"))
      (node (ref "ENTER") (pin "MX2") (pinfunction "P1_MX2") (pintype "bidirectional"))
      (node (ref "LEFT") (pin "MX2") (pinfunction "P1_MX2") (pintype "bidirectional"))
      (node (ref "U$1") (pin "36") (pinfunction "PF7(ADC7)_36") (pintype "bidirectional"))
      (node (ref "U$4") (pin "MX2") (pinfunction "P1_MX2") (pintype "bidirectional"))
      (node (ref "]") (pin "MX2") (pinfunction "P1_MX2") (pintype "bidirectional"))
    )
    (net (code "16") (name "C13") (class "Default")
      (node (ref "BCKSPC") (pin "MX2") (pinfunction "P1_MX2") (pintype "bidirectional"))
      (node (ref "DOWN") (pin "MX2") (pinfunction "P1_MX2") (pintype "bidirectional"))
      (node (ref "U$1") (pin "29") (pinfunction "PB5(ADC12)_29") (pintype "bidirectional"))
      (node (ref "U$2") (pin "MX2") (pinfunction "P1_MX2") (pintype "bidirectional"))
      (node (ref "U$3") (pin "MX2") (pinfunction "P1_MX2") (pintype "bidirectional"))
      (node (ref "U$5") (pin "MX2") (pinfunction "P1_MX2") (pintype "bidirectional"))
      (node (ref "UP") (pin "MX2") (pinfunction "P1_MX2") (pintype "bidirectional"))
      (node (ref "\\") (pin "MX2") (pinfunction "P1_MX2") (pintype "bidirectional"))
    )
    (net (code "17") (name "C15") (class "Default")
      (node (ref "DEL") (pin "MX2") (pinfunction "P1_MX2") (pintype "bidirectional"))
      (node (ref "PAGEDN") (pin "MX2") (pinfunction "P1_MX2") (pintype "bidirectional"))
      (node (ref "PAGEUP") (pin "MX2") (pinfunction "P1_MX2") (pintype "bidirectional"))
      (node (ref "RIGHT") (pin "MX2") (pinfunction "P1_MX2") (pintype "bidirectional"))
      (node (ref "U$1") (pin "30") (pinfunction "PB6(ADC13)_30") (pintype "bidirectional"))
      (node (ref "U1") (pin "E1") (pinfunction "E1_E1") (pintype "bidirectional"))
    )
    (net (code "18") (name "D+") (class "Default")
      (node (ref "R3") (pin "2") (pinfunction "2_2") (pintype "passive"))
      (node (ref "U$1") (pin "4") (pinfunction "D+_4") (pintype "bidirectional"))
    )
    (net (code "19") (name "D-") (class "Default")
      (node (ref "R2") (pin "2") (pinfunction "2_2") (pintype "passive"))
      (node (ref "U$1") (pin "3") (pinfunction "D-_3") (pintype "bidirectional"))
    )
    (net (code "20") (name "GND") (class "Default")
      (node (ref "C1") (pin "1") (pinfunction "1_1") (pintype "passive"))
      (node (ref "C11") (pin "1") (pinfunction "1_1") (pintype "passive"))
      (node (ref "C12") (pin "1") (pinfunction "1_1") (pintype "passive"))
      (node (ref "C2") (pin "1") (pinfunction "1_1") (pintype "passive"))
      (node (ref "C3") (pin "1") (pinfunction "1_1") (pintype "passive"))
      (node (ref "C4") (pin "1") (pinfunction "1_1") (pintype "passive"))
      (node (ref "C6") (pin "2") (pinfunction "2_2") (pintype "passive"))
      (node (ref "C7") (pin "2") (pinfunction "2_2") (pintype "passive"))
      (node (ref "C8") (pin "2") (pinfunction "2_2") (pintype "passive"))
      (node (ref "C9") (pin "1") (pinfunction "1_1") (pintype "passive"))
      (node (ref "J1") (pin "1") (pinfunction "1_1") (pintype "bidirectional"))
      (node (ref "J1") (pin "5") (pinfunction "5_5") (pintype "bidirectional"))
      (node (ref "J1") (pin "6") (pinfunction "6_6") (pintype "bidirectional"))
      (node (ref "R1") (pin "1") (pinfunction "1_1") (pintype "passive"))
      (node (ref "S1") (pin "1") (pinfunction "COM_1_1") (pintype "bidirectional"))
      (node (ref "S1") (pin "2") (pinfunction "COM_2_2") (pintype "bidirectional"))
      (node (ref "U$1") (pin "15") (pinfunction "GND_15") (pintype "bidirectional"))
      (node (ref "U$1") (pin "23") (pinfunction "GND_23") (pintype "bidirectional"))
      (node (ref "U$1") (pin "35") (pinfunction "GND_35") (pintype "bidirectional"))
      (node (ref "U$1") (pin "43") (pinfunction "GND_43") (pintype "bidirectional"))
      (node (ref "U$1") (pin "5") (pinfunction "UGND_5") (pintype "bidirectional"))
      (node (ref "U1") (pin "C1") (pinfunction "C1_C1") (pintype "bidirectional"))
      (node (ref "Y2") (pin "2") (pinfunction "GND_1_2") (pintype "bidirectional"))
      (node (ref "Y2") (pin "4") (pinfunction "GND_2_4") (pintype "bidirectional"))
    )
    (net (code "21") (name "Net-('-P0)") (class "Default")
      (node (ref "'") (pin "MX1") (pinfunction "P0_MX1") (pintype "bidirectional"))
      (node (ref "D19") (pin "2") (pinfunction "K_2") (pintype "bidirectional"))
    )
    (net (code "22") (name "Net-(,-P0)") (class "Default")
      (node (ref ",") (pin "MX1") (pinfunction "P0_MX1") (pintype "bidirectional"))
      (node (ref "D8") (pin "2") (pinfunction "K_2") (pintype "bidirectional"))
    )
    (net (code "23") (name "Net-(--P0)") (class "Default")
      (node (ref "-") (pin "MX1") (pinfunction "P0_MX1") (pintype "bidirectional"))
      (node (ref "D33") (pin "2") (pinfunction "K_2") (pintype "bidirectional"))
    )
    (net (code "24") (name "Net-(.-P0)") (class "Default")
      (node (ref ".") (pin "MX1") (pinfunction "P0_MX1") (pintype "bidirectional"))
      (node (ref "D8") (pin "1") (pinfunction "A_1") (pintype "bidirectional"))
    )
    (net (code "25") (name "Net-(/-P0)") (class "Default")
      (node (ref "/") (pin "MX1") (pinfunction "P0_MX1") (pintype "bidirectional"))
      (node (ref "D9") (pin "2") (pinfunction "K_2") (pintype "bidirectional"))
    )
    (net (code "26") (name "Net-(0-P0)") (class "Default")
      (node (ref "0") (pin "MX1") (pinfunction "P0_MX1") (pintype "bidirectional"))
      (node (ref "D33") (pin "1") (pinfunction "A_1") (pintype "bidirectional"))
    )
    (net (code "27") (name "Net-(1-P0)") (class "Default")
      (node (ref "1") (pin "MX1") (pinfunction "P0_MX1") (pintype "bidirectional"))
      (node (ref "D1") (pin "2") (pinfunction "K_2") (pintype "bidirectional"))
    )
    (net (code "28") (name "Net-(2-P0)") (class "Default")
      (node (ref "2") (pin "MX1") (pinfunction "P0_MX1") (pintype "bidirectional"))
      (node (ref "D29") (pin "1") (pinfunction "A_1") (pintype "bidirectional"))
    )
    (net (code "29") (name "Net-(3-P0)") (class "Default")
      (node (ref "3") (pin "MX1") (pinfunction "P0_MX1") (pintype "bidirectional"))
      (node (ref "D29") (pin "2") (pinfunction "K_2") (pintype "bidirectional"))
    )
    (net (code "30") (name "Net-(4-P0)") (class "Default")
      (node (ref "4") (pin "MX1") (pinfunction "P0_MX1") (pintype "bidirectional"))
      (node (ref "D30") (pin "1") (pinfunction "A_1") (pintype "bidirectional"))
    )
    (net (code "31") (name "Net-(5-P0)") (class "Default")
      (node (ref "5") (pin "MX1") (pinfunction "P0_MX1") (pintype "bidirectional"))
      (node (ref "D30") (pin "2") (pinfunction "K_2") (pintype "bidirectional"))
    )
    (net (code "32") (name "Net-(6-P0)") (class "Default")
      (node (ref "6") (pin "MX1") (pinfunction "P0_MX1") (pintype "bidirectional"))
      (node (ref "D31") (pin "1") (pinfunction "A_1") (pintype "bidirectional"))
    )
    (net (code "33") (name "Net-(7-P0)") (class "Default")
      (node (ref "7") (pin "MX1") (pinfunction "P0_MX1") (pintype "bidirectional"))
      (node (ref "D31") (pin "2") (pinfunction "K_2") (pintype "bidirectional"))
    )
    (net (code "34") (name "Net-(8-P0)") (class "Default")
      (node (ref "8") (pin "MX1") (pinfunction "P0_MX1") (pintype "bidirectional"))
      (node (ref "D32") (pin "1") (pinfunction "A_1") (pintype "bidirectional"))
    )
    (net (code "35") (name "Net-(9-P0)") (class "Default")
      (node (ref "9") (pin "MX1") (pinfunction "P0_MX1") (pintype "bidirectional"))
      (node (ref "D32") (pin "2") (pinfunction "K_2") (pintype "bidirectional"))
    )
    (net (code "36") (name "Net-(=-P0)") (class "Default")
      (node (ref "=") (pin "MX1") (pinfunction "P0_MX1") (pintype "bidirectional"))
      (node (ref "D34") (pin "1") (pinfunction "A_1") (pintype "bidirectional"))
    )
    (net (code "37") (name "Net-(A-P0)") (class "Default")
      (node (ref "A") (pin "MX1") (pinfunction "P0_MX1") (pintype "bidirectional"))
      (node (ref "D3") (pin "2") (pinfunction "K_2") (pintype "bidirectional"))
    )
    (net (code "38") (name "Net-(ALT-P0)") (class "Default")
      (node (ref "ALT") (pin "MX1") (pinfunction "P0_MX1") (pintype "bidirectional"))
      (node (ref "D12") (pin "1") (pinfunction "A_1") (pintype "bidirectional"))
      (node (ref "U$13") (pin "MX1") (pinfunction "P0_MX1") (pintype "bidirectional"))
      (node (ref "U$7") (pin "MX1") (pinfunction "P0_MX1") (pintype "bidirectional"))
    )
    (net (code "39") (name "Net-(B-P0)") (class "Default")
      (node (ref "B") (pin "MX1") (pinfunction "P0_MX1") (pintype "bidirectional"))
      (node (ref "D6") (pin "1") (pinfunction "A_1") (pintype "bidirectional"))
    )
    (net (code "40") (name "Net-(BCKSPC-P0)") (class "Default")
      (node (ref "BCKSPC") (pin "MX1") (pinfunction "P0_MX1") (pintype "bidirectional"))
      (node (ref "D28") (pin "1") (pinfunction "A_1") (pintype "bidirectional"))
      (node (ref "U$3") (pin "MX1") (pinfunction "P0_MX1") (pintype "bidirectional"))
    )
    (net (code "41") (name "Net-(C-P0)") (class "Default")
      (node (ref "C") (pin "MX1") (pinfunction "P0_MX1") (pintype "bidirectional"))
      (node (ref "D5") (pin "1") (pinfunction "A_1") (pintype "bidirectional"))
    )
    (net (code "42") (name "Net-(CAPS-P0)") (class "Default")
      (node (ref "CAPS") (pin "MX1") (pinfunction "P0_MX1") (pintype "bidirectional"))
      (node (ref "D3") (pin "1") (pinfunction "A_1") (pintype "bidirectional"))
      (node (ref "U$10") (pin "MX1") (pinfunction "P0_MX1") (pintype "bidirectional"))
    )
    (net (code "43") (name "Net-(D-P0)") (class "Default")
      (node (ref "D") (pin "MX1") (pinfunction "P0_MX1") (pintype "bidirectional"))
      (node (ref "D15") (pin "2") (pinfunction "K_2") (pintype "bidirectional"))
    )
    (net (code "44") (name "Net-(D1-A)") (class "Default")
      (node (ref "D1") (pin "1") (pinfunction "A_1") (pintype "bidirectional"))
      (node (ref "ESC") (pin "MX1") (pinfunction "P0_MX1") (pintype "bidirectional"))
    )
    (net (code "45") (name "Net-(D2-A)") (class "Default")
      (node (ref "D2") (pin "1") (pinfunction "A_1") (pintype "bidirectional"))
      (node (ref "Q") (pin "MX1") (pinfunction "P0_MX1") (pintype "bidirectional"))
    )
    (net (code "46") (name "Net-(D2-K)") (class "Default")
      (node (ref "D2") (pin "2") (pinfunction "K_2") (pintype "bidirectional"))
      (node (ref "TAB") (pin "MX1") (pinfunction "P0_MX1") (pintype "bidirectional"))
    )
    (net (code "47") (name "Net-(D4-A)") (class "Default")
      (node (ref "D4") (pin "1") (pinfunction "A_1") (pintype "bidirectional"))
      (node (ref "Z") (pin "MX1") (pinfunction "P0_MX1") (pintype "bidirectional"))
    )
    (net (code "48") (name "Net-(D4-K)") (class "Default")
      (node (ref "D4") (pin "2") (pinfunction "K_2") (pintype "bidirectional"))
      (node (ref "SHIFT") (pin "MX1") (pinfunction "P0_MX1") (pintype "bidirectional"))
    )
    (net (code "49") (name "Net-(D5-K)") (class "Default")
      (node (ref "D5") (pin "2") (pinfunction "K_2") (pintype "bidirectional"))
      (node (ref "X") (pin "MX1") (pinfunction "P0_MX1") (pintype "bidirectional"))
    )
    (net (code "50") (name "Net-(D6-K)") (class "Default")
      (node (ref "D6") (pin "2") (pinfunction "K_2") (pintype "bidirectional"))
      (node (ref "V") (pin "MX1") (pinfunction "P0_MX1") (pintype "bidirectional"))
    )
    (net (code "51") (name "Net-(D7-A)") (class "Default")
      (node (ref "D7") (pin "1") (pinfunction "A_1") (pintype "bidirectional"))
      (node (ref "M") (pin "MX1") (pinfunction "P0_MX1") (pintype "bidirectional"))
    )
    (net (code "52") (name "Net-(D7-K)") (class "Default")
      (node (ref "D7") (pin "2") (pinfunction "K_2") (pintype "bidirectional"))
      (node (ref "N") (pin "MX1") (pinfunction "P0_MX1") (pintype "bidirectional"))
    )
    (net (code "53") (name "Net-(D9-A)") (class "Default")
      (node (ref "D9") (pin "1") (pinfunction "A_1") (pintype "bidirectional"))
      (node (ref "RSHIFT") (pin "MX1") (pinfunction "P0_MX1") (pintype "bidirectional"))
    )
    (net (code "54") (name "Net-(D10-A)") (class "Default")
      (node (ref "D10") (pin "1") (pinfunction "A_1") (pintype "bidirectional"))
      (node (ref "PAGEDN") (pin "MX1") (pinfunction "P0_MX1") (pintype "bidirectional"))
    )
    (net (code "55") (name "Net-(D10-K)") (class "Default")
      (node (ref "D10") (pin "2") (pinfunction "K_2") (pintype "bidirectional"))
      (node (ref "UP") (pin "MX1") (pinfunction "P0_MX1") (pintype "bidirectional"))
    )
    (net (code "56") (name "Net-(D11-A)") (class "Default")
      (node (ref "D11") (pin "1") (pinfunction "A_1") (pintype "bidirectional"))
      (node (ref "U$16") (pin "MX1") (pinfunction "P0_MX1") (pintype "bidirectional"))
    )
    (net (code "57") (name "Net-(D11-K)") (class "Default")
      (node (ref "D11") (pin "2") (pinfunction "K_2") (pintype "bidirectional"))
      (node (ref "U$12") (pin "MX1") (pinfunction "P0_MX1") (pintype "bidirectional"))
      (node (ref "U$6") (pin "MX1") (pinfunction "P0_MX1") (pintype "bidirectional"))
      (node (ref "WIN") (pin "MX1") (pinfunction "P0_MX1") (pintype "bidirectional"))
    )
    (net (code "58") (name "Net-(D13-A)") (class "Default")
      (node (ref "D13") (pin "1") (pinfunction "A_1") (pintype "bidirectional"))
      (node (ref "SPACE") (pin "MX1") (pinfunction "P0_MX1") (pintype "bidirectional"))
      (node (ref "U$11") (pin "MX1") (pinfunction "P0_MX1") (pintype "bidirectional"))
    )
    (net (code "59") (name "Net-(D13-K)") (class "Default")
      (node (ref "D13") (pin "2") (pinfunction "K_2") (pintype "bidirectional"))
      (node (ref "RALT") (pin "MX1") (pinfunction "P0_MX1") (pintype "bidirectional"))
      (node (ref "U$14") (pin "MX1") (pinfunction "P0_MX1") (pintype "bidirectional"))
      (node (ref "U$8") (pin "MX1") (pinfunction "P0_MX1") (pintype "bidirectional"))
    )
    (net (code "60") (name "Net-(D14-A)") (class "Default")
      (node (ref "D14") (pin "1") (pinfunction "A_1") (pintype "bidirectional"))
      (node (ref "FN") (pin "MX1") (pinfunction "P0_MX1") (pintype "bidirectional"))
      (node (ref "U$15") (pin "MX1") (pinfunction "P0_MX1") (pintype "bidirectional"))
      (node (ref "U$9") (pin "MX1") (pinfunction "P0_MX1") (pintype "bidirectional"))
    )
    (net (code "61") (name "Net-(D14-K)") (class "Default")
      (node (ref "D14") (pin "2") (pinfunction "K_2") (pintype "bidirectional"))
      (node (ref "LEFT") (pin "MX1") (pinfunction "P0_MX1") (pintype "bidirectional"))
    )
    (net (code "62") (name "Net-(D15-A)") (class "Default")
      (node (ref "D15") (pin "1") (pinfunction "A_1") (pintype "bidirectional"))
      (node (ref "S") (pin "MX1") (pinfunction "P0_MX1") (pintype "bidirectional"))
    )
    (net (code "63") (name "Net-(D16-A)") (class "Default")
      (node (ref "D16") (pin "1") (pinfunction "A_1") (pintype "bidirectional"))
      (node (ref "F") (pin "MX1") (pinfunction "P0_MX1") (pintype "bidirectional"))
    )
    (net (code "64") (name "Net-(D16-K)") (class "Default")
      (node (ref "D16") (pin "2") (pinfunction "K_2") (pintype "bidirectional"))
      (node (ref "G") (pin "MX1") (pinfunction "P0_MX1") (pintype "bidirectional"))
    )
    (net (code "65") (name "Net-(D17-A)") (class "Default")
      (node (ref "D17") (pin "1") (pinfunction "A_1") (pintype "bidirectional"))
      (node (ref "H") (pin "MX1") (pinfunction "P0_MX1") (pintype "bidirectional"))
    )
    (net (code "66") (name "Net-(D17-K)") (class "Default")
      (node (ref "D17") (pin "2") (pinfunction "K_2") (pintype "bidirectional"))
      (node (ref "J") (pin "MX1") (pinfunction "P0_MX1") (pintype "bidirectional"))
    )
    (net (code "67") (name "Net-(D18-A)") (class "Default")
      (node (ref "D18") (pin "1") (pinfunction "A_1") (pintype "bidirectional"))
      (node (ref "K") (pin "MX1") (pinfunction "P0_MX1") (pintype "bidirectional"))
    )
    (net (code "68") (name "Net-(D18-K)") (class "Default")
      (node (ref "D18") (pin "2") (pinfunction "K_2") (pintype "bidirectional"))
      (node (ref "L") (pin "MX1") (pinfunction "P0_MX1") (pintype "bidirectional"))
    )
    (net (code "69") (name "Net-(D19-A)") (class "Default")
      (node (ref "D19") (pin "1") (pinfunction "A_1") (pintype "bidirectional"))
      (node (ref "SEMICOL") (pin "MX1") (pinfunction "P0_MX1") (pintype "bidirectional"))
    )
    (net (code "70") (name "Net-(D20-A)") (class "Default")
      (node (ref "D20") (pin "1") (pinfunction "A_1") (pintype "bidirectional"))
      (node (ref "ENTER") (pin "MX1") (pinfunction "P0_MX1") (pintype "bidirectional"))
      (node (ref "U$4") (pin "MX1") (pinfunction "P0_MX1") (pintype "bidirectional"))
    )
    (net (code "71") (name "Net-(D20-K)") (class "Default")
      (node (ref "D20") (pin "2") (pinfunction "K_2") (pintype "bidirectional"))
      (node (ref "U$5") (pin "MX1") (pinfunction "P0_MX1") (pintype "bidirectional"))
      (node (ref "\\") (pin "MX1") (pinfunction "P0_MX1") (pintype "bidirectional"))
    )
    (net (code "72") (name "Net-(D21-K)") (class "Default")
      (node (ref "D21") (pin "2") (pinfunction "K_2") (pintype "bidirectional"))
      (node (ref "PAGEUP") (pin "MX1") (pinfunction "P0_MX1") (pintype "bidirectional"))
    )
    (net (code "73") (name "Net-(D22-A)") (class "Default")
      (node (ref "D22") (pin "1") (pinfunction "A_1") (pintype "bidirectional"))
      (node (ref "E") (pin "MX1") (pinfunction "P0_MX1") (pintype "bidirectional"))
    )
    (net (code "74") (name "Net-(D22-K)") (class "Default")
      (node (ref "D22") (pin "2") (pinfunction "K_2") (pintype "bidirectional"))
      (node (ref "W") (pin "MX1") (pinfunction "P0_MX1") (pintype "bidirectional"))
    )
    (net (code "75") (name "Net-(D23-A)") (class "Default")
      (node (ref "D23") (pin "1") (pinfunction "A_1") (pintype "bidirectional"))
      (node (ref "T") (pin "MX1") (pinfunction "P0_MX1") (pintype "bidirectional"))
    )
    (net (code "76") (name "Net-(D23-K)") (class "Default")
      (node (ref "D23") (pin "2") (pinfunction "K_2") (pintype "bidirectional"))
      (node (ref "R") (pin "MX1") (pinfunction "P0_MX1") (pintype "bidirectional"))
    )
    (net (code "77") (name "Net-(D24-A)") (class "Default")
      (node (ref "D24") (pin "1") (pinfunction "A_1") (pintype "bidirectional"))
      (node (ref "U") (pin "MX1") (pinfunction "P0_MX1") (pintype "bidirectional"))
    )
    (net (code "78") (name "Net-(D24-K)") (class "Default")
      (node (ref "D24") (pin "2") (pinfunction "K_2") (pintype "bidirectional"))
      (node (ref "Y") (pin "MX1") (pinfunction "P0_MX1") (pintype "bidirectional"))
    )
    (net (code "79") (name "Net-(D25-A)") (class "Default")
      (node (ref "D25") (pin "1") (pinfunction "A_1") (pintype "bidirectional"))
      (node (ref "O") (pin "MX1") (pinfunction "P0_MX1") (pintype "bidirectional"))
    )
    (net (code "80") (name "Net-(D25-K)") (class "Default")
      (node (ref "D25") (pin "2") (pinfunction "K_2") (pintype "bidirectional"))
      (node (ref "I") (pin "MX1") (pinfunction "P0_MX1") (pintype "bidirectional"))
    )
    (net (code "81") (name "Net-(D26-A)") (class "Default")
      (node (ref "D26") (pin "1") (pinfunction "A_1") (pintype "bidirectional"))
      (node (ref "[") (pin "MX1") (pinfunction "P0_MX1") (pintype "bidirectional"))
    )
    (net (code "82") (name "Net-(D26-K)") (class "Default")
      (node (ref "D26") (pin "2") (pinfunction "K_2") (pintype "bidirectional"))
      (node (ref "P") (pin "MX1") (pinfunction "P0_MX1") (pintype "bidirectional"))
    )
    (net (code "83") (name "Net-(D27-K)") (class "Default")
      (node (ref "D27") (pin "2") (pinfunction "K_2") (pintype "bidirectional"))
      (node (ref "]") (pin "MX1") (pinfunction "P0_MX1") (pintype "bidirectional"))
    )
    (net (code "84") (name "Net-(D28-K)") (class "Default")
      (node (ref "D28") (pin "2") (pinfunction "K_2") (pintype "bidirectional"))
      (node (ref "DEL") (pin "MX1") (pinfunction "P0_MX1") (pintype "bidirectional"))
    )
    (net (code "85") (name "Net-(D34-K)") (class "Default")
      (node (ref "D34") (pin "2") (pinfunction "K_2") (pintype "bidirectional"))
      (node (ref "U$2") (pin "MX1") (pinfunction "P0_MX1") (pintype "bidirectional"))
    )
    (net (code "86") (name "Net-(D35-K)") (class "Default")
      (node (ref "D35") (pin "2") (pinfunction "K_2") (pintype "bidirectional"))
      (node (ref "U1") (pin "D1") (pinfunction "D1_D1") (pintype "bidirectional"))
    )
    (net (code "87") (name "Net-(D36-A)") (class "Default")
      (node (ref "D36") (pin "1") (pinfunction "A_1") (pintype "bidirectional"))
      (node (ref "DOWN") (pin "MX1") (pinfunction "P0_MX1") (pintype "bidirectional"))
    )
    (net (code "88") (name "Net-(D36-K)") (class "Default")
      (node (ref "D36") (pin "2") (pinfunction "K_2") (pintype "bidirectional"))
      (node (ref "RIGHT") (pin "MX1") (pinfunction "P0_MX1") (pintype "bidirectional"))
    )
    (net (code "89") (name "Net-(J1-Pad2)") (class "Default")
      (node (ref "J1") (pin "2") (pinfunction "2_2") (pintype "bidirectional"))
      (node (ref "R3") (pin "1") (pinfunction "1_1") (pintype "passive"))
    )
    (net (code "90") (name "Net-(J1-Pad3)") (class "Default")
      (node (ref "J1") (pin "3") (pinfunction "3_3") (pintype "bidirectional"))
      (node (ref "R2") (pin "1") (pinfunction "1_1") (pintype "passive"))
    )
    (net (code "91") (name "Net-(S1-NO_1)") (class "Default")
      (node (ref "R4") (pin "1") (pinfunction "1_1") (pintype "passive"))
      (node (ref "S1") (pin "3") (pinfunction "NO_1_3") (pintype "bidirectional"))
      (node (ref "S1") (pin "4") (pinfunction "NO_2_4") (pintype "bidirectional"))
      (node (ref "U$1") (pin "13") (pinfunction "~{RESET}_13") (pintype "bidirectional"))
    )
    (net (code "92") (name "Net-(U$1-PE2{slash}~{HWB})") (class "Default")
      (node (ref "R1") (pin "2") (pinfunction "2_2") (pintype "passive"))
      (node (ref "U$1") (pin "33") (pinfunction "PE2/~{HWB}_33") (pintype "bidirectional"))
    )
    (net (code "93") (name "Net-(U$1-UCAP)") (class "Default")
      (node (ref "C1") (pin "2") (pinfunction "2_2") (pintype "passive"))
      (node (ref "U$1") (pin "6") (pinfunction "UCAP_6") (pintype "bidirectional"))
    )
    (net (code "94") (name "Net-(U$1-XTAL1)") (class "Default")
      (node (ref "C6") (pin "1") (pinfunction "1_1") (pintype "passive"))
      (node (ref "U$1") (pin "17") (pinfunction "XTAL1_17") (pintype "bidirectional"))
      (node (ref "Y2") (pin "1") (pinfunction "CRYSTAL_1_1") (pintype "bidirectional"))
    )
    (net (code "95") (name "Net-(U$1-XTAL2)") (class "Default")
      (node (ref "C7") (pin "1") (pinfunction "1_1") (pintype "passive"))
      (node (ref "U$1") (pin "16") (pinfunction "XTAL2_16") (pintype "bidirectional"))
      (node (ref "Y2") (pin "3") (pinfunction "CRYSTAL_2_3") (pintype "bidirectional"))
    )
    (net (code "96") (name "R0") (class "Default")
      (node (ref "D1") (pin "3") (pinfunction "K/A_3") (pintype "bidirectional"))
      (node (ref "D29") (pin "3") (pinfunction "K/A_3") (pintype "bidirectional"))
      (node (ref "D30") (pin "3") (pinfunction "K/A_3") (pintype "bidirectional"))
      (node (ref "D31") (pin "3") (pinfunction "K/A_3") (pintype "bidirectional"))
      (node (ref "D32") (pin "3") (pinfunction "K/A_3") (pintype "bidirectional"))
      (node (ref "D33") (pin "3") (pinfunction "K/A_3") (pintype "bidirectional"))
      (node (ref "D34") (pin "3") (pinfunction "K/A_3") (pintype "bidirectional"))
      (node (ref "D35") (pin "3") (pinfunction "K/A_3") (pintype "bidirectional"))
      (node (ref "U$1") (pin "8") (pinfunction "PB0(SS)_8") (pintype "bidirectional"))
    )
    (net (code "97") (name "R1") (class "Default")
      (node (ref "D2") (pin "3") (pinfunction "K/A_3") (pintype "bidirectional"))
      (node (ref "D22") (pin "3") (pinfunction "K/A_3") (pintype "bidirectional"))
      (node (ref "D23") (pin "3") (pinfunction "K/A_3") (pintype "bidirectional"))
      (node (ref "D24") (pin "3") (pinfunction "K/A_3") (pintype "bidirectional"))
      (node (ref "D25") (pin "3") (pinfunction "K/A_3") (pintype "bidirectional"))
      (node (ref "D26") (pin "3") (pinfunction "K/A_3") (pintype "bidirectional"))
      (node (ref "D27") (pin "3") (pinfunction "K/A_3") (pintype "bidirectional"))
      (node (ref "D28") (pin "3") (pinfunction "K/A_3") (pintype "bidirectional"))
      (node (ref "U$1") (pin "9") (pinfunction "PB1(SCK)_9") (pintype "bidirectional"))
    )
    (net (code "98") (name "R2") (class "Default")
      (node (ref "D15") (pin "3") (pinfunction "K/A_3") (pintype "bidirectional"))
      (node (ref "D16") (pin "3") (pinfunction "K/A_3") (pintype "bidirectional"))
      (node (ref "D17") (pin "3") (pinfunction "K/A_3") (pintype "bidirectional"))
      (node (ref "D18") (pin "3") (pinfunction "K/A_3") (pintype "bidirectional"))
      (node (ref "D19") (pin "3") (pinfunction "K/A_3") (pintype "bidirectional"))
      (node (ref "D20") (pin "3") (pinfunction "K/A_3") (pintype "bidirectional"))
      (node (ref "D21") (pin "3") (pinfunction "K/A_3") (pintype "bidirectional"))
      (node (ref "D3") (pin "3") (pinfunction "K/A_3") (pintype "bidirectional"))
      (node (ref "U$1") (pin "10") (pinfunction "PB2(MOSI)_10") (pintype "bidirectional"))
    )
    (net (code "99") (name "R3") (class "Default")
      (node (ref "D10") (pin "3") (pinfunction "K/A_3") (pintype "bidirectional"))
      (node (ref "D4") (pin "3") (pinfunction "K/A_3") (pintype "bidirectional"))
      (node (ref "D5") (pin "3") (pinfunction "K/A_3") (pintype "bidirectional"))
      (node (ref "D6") (pin "3") (pinfunction "K/A_3") (pintype "bidirectional"))
      (node (ref "D7") (pin "3") (pinfunction "K/A_3") (pintype "bidirectional"))
      (node (ref "D8") (pin "3") (pinfunction "K/A_3") (pintype "bidirectional"))
      (node (ref "D9") (pin "3") (pinfunction "K/A_3") (pintype "bidirectional"))
      (node (ref "U$1") (pin "11") (pinfunction "PB3(MISO)_11") (pintype "bidirectional"))
    )
    (net (code "100") (name "R4") (class "Default")
      (node (ref "D11") (pin "3") (pinfunction "K/A_3") (pintype "bidirectional"))
      (node (ref "D12") (pin "3") (pinfunction "K/A_3") (pintype "bidirectional"))
      (node (ref "D13") (pin "3") (pinfunction "K/A_3") (pintype "bidirectional"))
      (node (ref "D14") (pin "3") (pinfunction "K/A_3") (pintype "bidirectional"))
      (node (ref "D36") (pin "3") (pinfunction "K/A_3") (pintype "bidirectional"))
      (node (ref "U$1") (pin "39") (pinfunction "PF4(ADC4)_39") (pintype "bidirectional"))
    )
    (net (code "101") (name "VCC") (class "Default")
      (node (ref "C11") (pin "2") (pinfunction "2_2") (pintype "passive"))
      (node (ref "C12") (pin "2") (pinfunction "2_2") (pintype "passive"))
      (node (ref "C2") (pin "2") (pinfunction "2_2") (pintype "passive"))
      (node (ref "C3") (pin "2") (pinfunction "2_2") (pintype "passive"))
      (node (ref "C4") (pin "2") (pinfunction "2_2") (pintype "passive"))
      (node (ref "J1") (pin "4") (pinfunction "4_4") (pintype "bidirectional"))
      (node (ref "R4") (pin "2") (pinfunction "2_2") (pintype "passive"))
      (node (ref "R5") (pin "2") (pinfunction "2_2") (pintype "passive"))
      (node (ref "R6") (pin "1") (pinfunction "1_1") (pintype "passive"))
      (node (ref "U$1") (pin "14") (pinfunction "VCC_14") (pintype "bidirectional"))
      (node (ref "U$1") (pin "2") (pinfunction "UVCC_2") (pintype "bidirectional"))
      (node (ref "U$1") (pin "24") (pinfunction "AVCC_24") (pintype "bidirectional"))
      (node (ref "U$1") (pin "34") (pinfunction "VCC_34") (pintype "bidirectional"))
      (node (ref "U$1") (pin "44") (pinfunction "AVCC_44") (pintype "bidirectional"))
      (node (ref "U$1") (pin "7") (pinfunction "VBUS_7") (pintype "bidirectional"))
    )
    (net (code "102") (name "unconnected-(D12-K-Pad2)") (class "Default")
      (node (ref "D12") (pin "2") (pinfunction "K_2") (pintype "bidirectional"))
    )
    (net (code "103") (name "unconnected-(D21-A-Pad1)") (class "Default")
      (node (ref "D21") (pin "1") (pinfunction "A_1") (pintype "bidirectional"))
    )
    (net (code "104") (name "unconnected-(D27-A-Pad1)") (class "Default")
      (node (ref "D27") (pin "1") (pinfunction "A_1") (pintype "bidirectional"))
    )
    (net (code "105") (name "unconnected-(D35-A-Pad1)") (class "Default")
      (node (ref "D35") (pin "1") (pinfunction "A_1") (pintype "bidirectional"))
    )
    (net (code "106") (name "unconnected-(U$1-AREF-Pad42)") (class "Default")
      (node (ref "U$1") (pin "42") (pinfunction "AREF_42") (pintype "bidirectional"))
    )
    (net (code "107") (name "unconnected-(U$1-PB7-Pad12)") (class "Default")
      (node (ref "U$1") (pin "12") (pinfunction "PB7_12") (pintype "bidirectional"))
    )
    (net (code "108") (name "unconnected-(U$1-PF5(ADC5)-Pad38)") (class "Default")
      (node (ref "U$1") (pin "38") (pinfunction "PF5(ADC5)_38") (pintype "bidirectional"))
    )
    (net (code "109") (name "unconnected-(U$1-PF6(ADC6)-Pad37)") (class "Default")
      (node (ref "U$1") (pin "37") (pinfunction "PF6(ADC6)_37") (pintype "bidirectional"))
    )
    (net (code "110") (name "unconnected-(U1-PadMH1)") (class "Default")
      (node (ref "U1") (pin "MH1") (pinfunction "MH1_MH1") (pintype "bidirectional"))
    )
    (net (code "111") (name "unconnected-(U1-PadMH2)") (class "Default")
      (node (ref "U1") (pin "MH2") (pinfunction "MH2_MH2") (pintype "bidirectional"))
    )
  )
)
